# test_circuit1.net
KiCad netlist of a schematic drawn in EAGLE
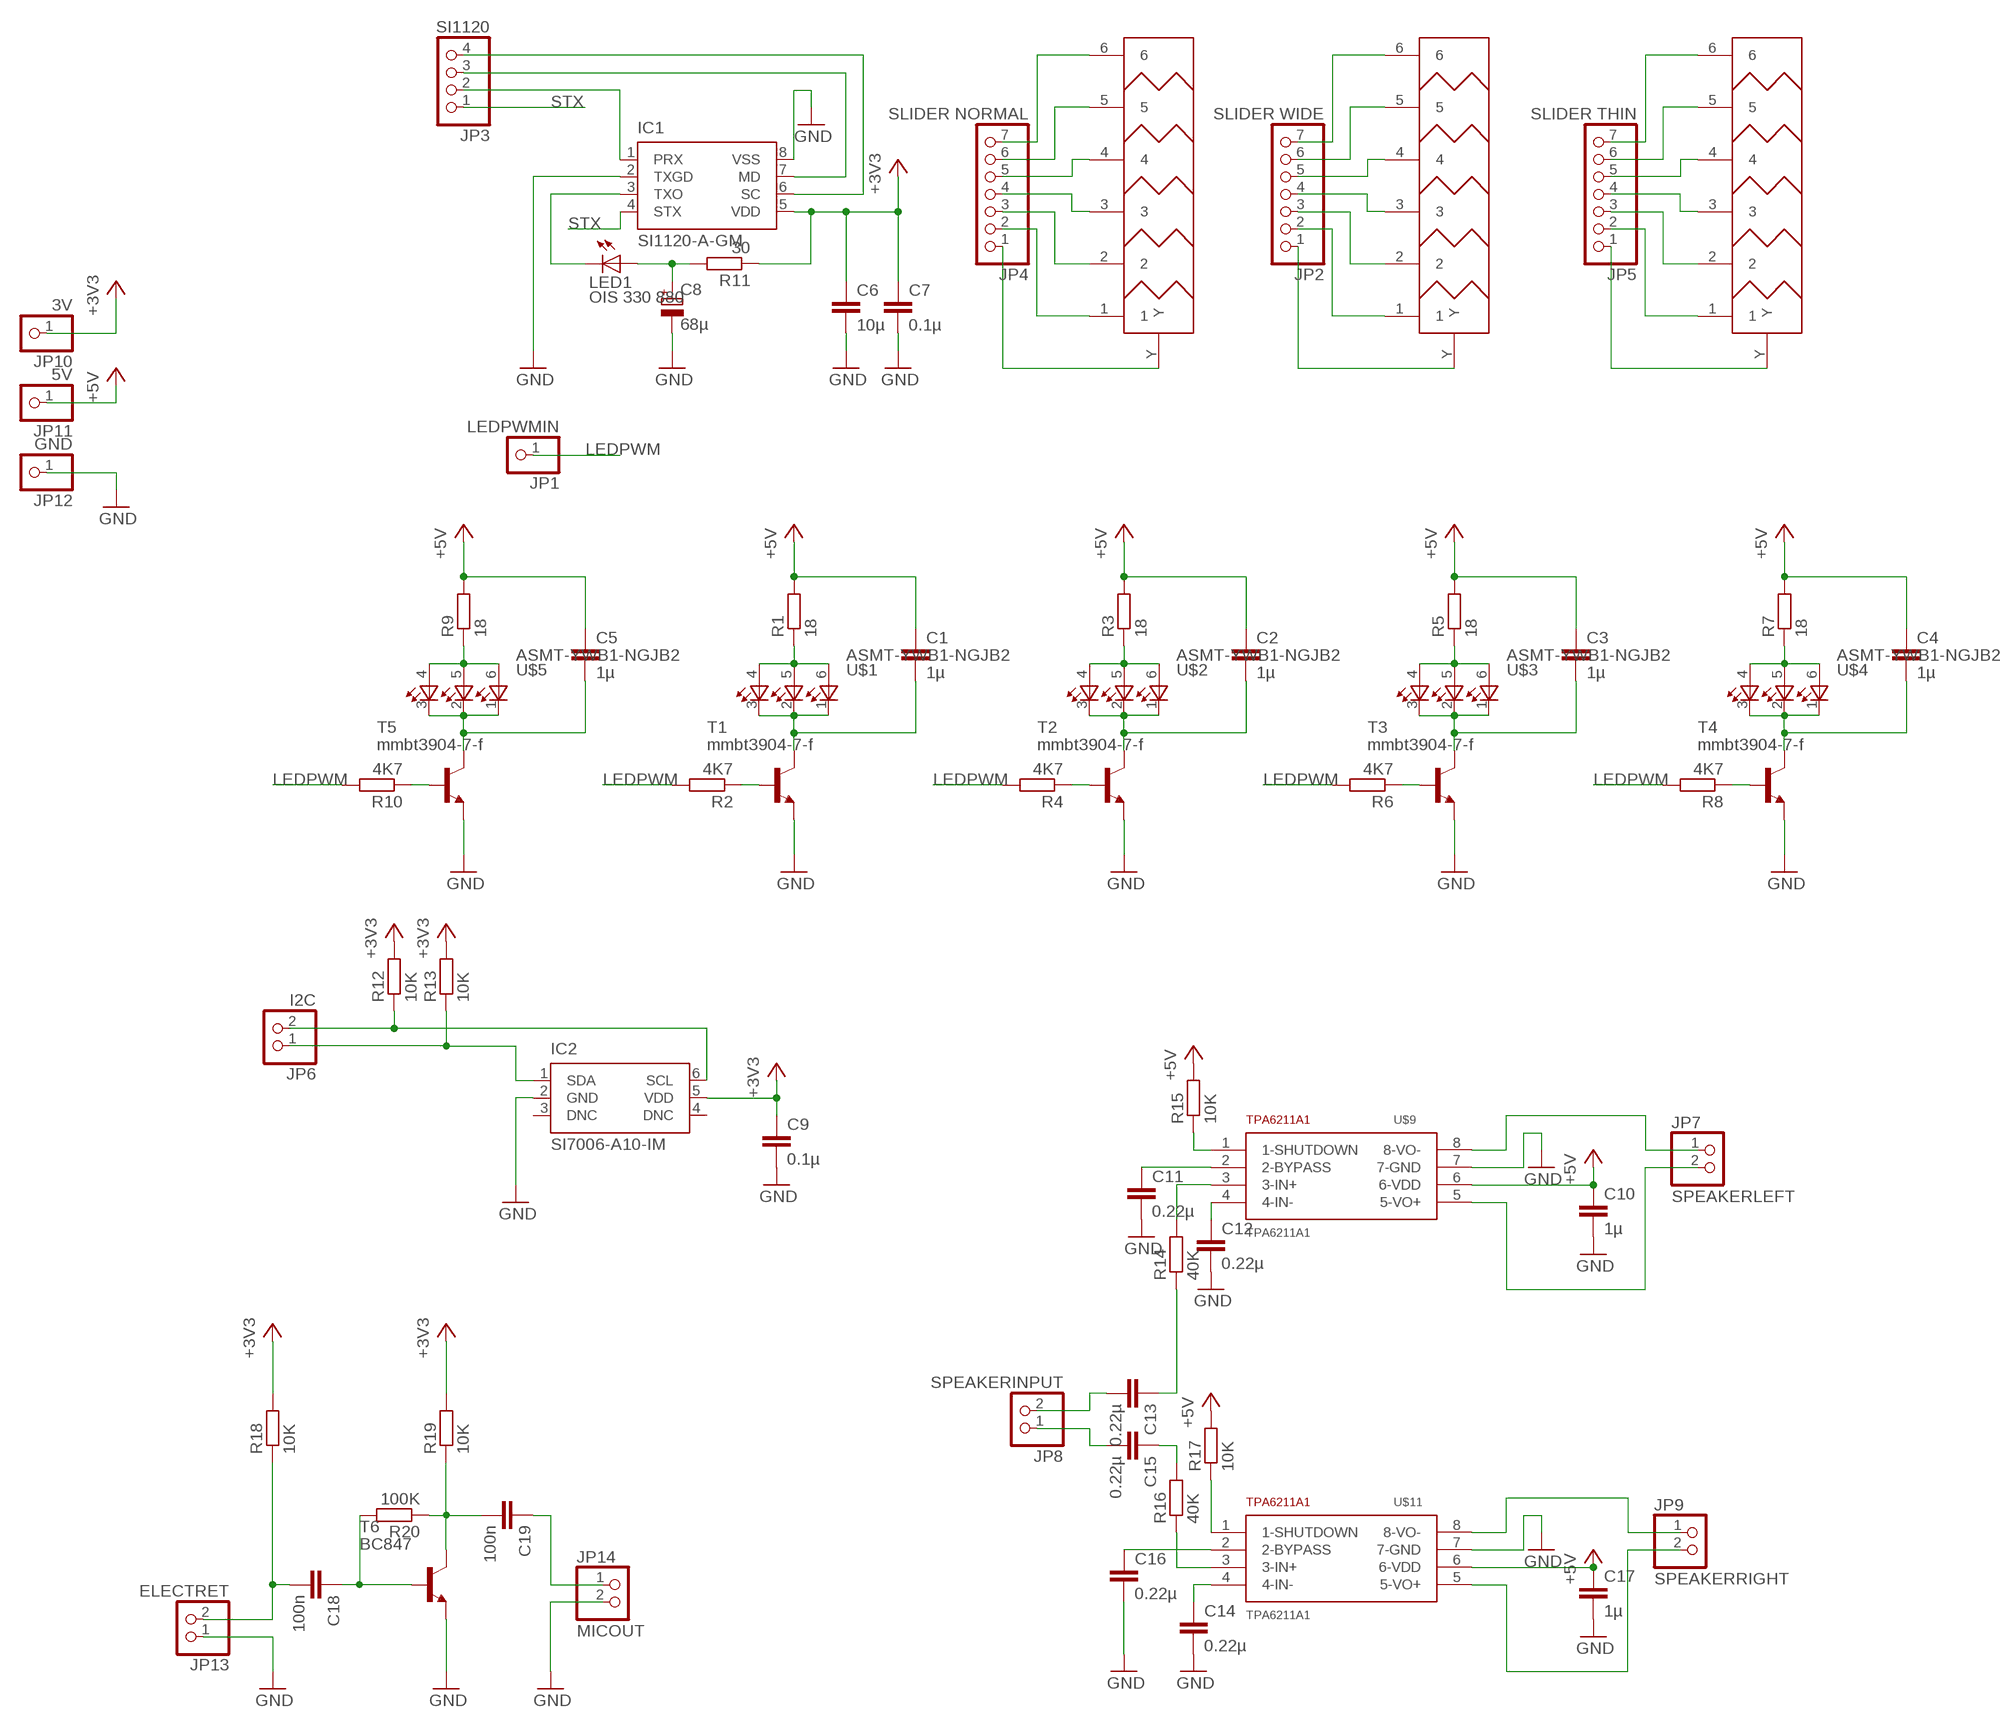
[diagram p0: schematic, sheet 1]

(export (version "E")
  (design (tool "Eeschema 10.0.6"))
  (components
    (comp (ref "C1")
      (value "1µ")
      (footprint "eagle-import:C0805")
      (libsource (lib "eagle-import") (part "C-EUC0805"))
    )
    (comp (ref "C2")
      (value "1µ")
      (footprint "eagle-import:C0805")
      (libsource (lib "eagle-import") (part "C-EUC0805"))
    )
    (comp (ref "C3")
      (value "1µ")
      (footprint "eagle-import:C0805")
      (libsource (lib "eagle-import") (part "C-EUC0805"))
    )
    (comp (ref "C4")
      (value "1µ")
      (footprint "eagle-import:C0805")
      (libsource (lib "eagle-import") (part "C-EUC0805"))
    )
    (comp (ref "C5")
      (value "1µ")
      (footprint "eagle-import:C0805")
      (libsource (lib "eagle-import") (part "C-EUC0805"))
    )
    (comp (ref "C6")
      (value "10µ")
      (footprint "eagle-import:C0805")
      (libsource (lib "eagle-import") (part "C-EUC0805"))
    )
    (comp (ref "C7")
      (value "0.1µ")
      (footprint "eagle-import:C0805")
      (libsource (lib "eagle-import") (part "C-EUC0805"))
    )
    (comp (ref "C8")
      (value "68µ")
      (footprint "eagle-import:E2,5-7")
      (libsource (lib "eagle-import") (part "CPOL-EUE2.5-7"))
    )
    (comp (ref "C9")
      (value "0.1µ")
      (footprint "eagle-import:C0805")
      (libsource (lib "eagle-import") (part "C-EUC0805"))
    )
    (comp (ref "C10")
      (value "1µ")
      (footprint "eagle-import:C0805")
      (libsource (lib "eagle-import") (part "C-EUC0805"))
    )
    (comp (ref "C11")
      (value "0.22µ")
      (footprint "eagle-import:C0805")
      (libsource (lib "eagle-import") (part "C-EUC0805"))
    )
    (comp (ref "C12")
      (value "0.22µ")
      (footprint "eagle-import:C0805")
      (libsource (lib "eagle-import") (part "C-EUC0805"))
    )
    (comp (ref "C13")
      (value "0.22µ")
      (footprint "eagle-import:C0805")
      (libsource (lib "eagle-import") (part "C-EUC0805"))
    )
    (comp (ref "C14")
      (value "0.22µ")
      (footprint "eagle-import:C0805")
      (libsource (lib "eagle-import") (part "C-EUC0805"))
    )
    (comp (ref "C15")
      (value "0.22µ")
      (footprint "eagle-import:C0805")
      (libsource (lib "eagle-import") (part "C-EUC0805"))
    )
    (comp (ref "C16")
      (value "0.22µ")
      (footprint "eagle-import:C0805")
      (libsource (lib "eagle-import") (part "C-EUC0805"))
    )
    (comp (ref "C17")
      (value "1µ")
      (footprint "eagle-import:C0805")
      (libsource (lib "eagle-import") (part "C-EUC0805"))
    )
    (comp (ref "C18")
      (value "100n")
      (footprint "eagle-import:C0805")
      (libsource (lib "eagle-import") (part "C-EUC0805"))
    )
    (comp (ref "C19")
      (value "100n")
      (footprint "eagle-import:C0805")
      (libsource (lib "eagle-import") (part "C-EUC0805"))
    )
    (comp (ref "IC1")
      (value "SI1120-A-GM")
      (footprint "eagle-import:ODFN8-3X3")
      (fields (field (name "MF") "Silicon Labs") (field (name "MPN") "Si1120-A-GM"))
      (libsource (lib "eagle-import") (part "SI1120-A-GM"))
    )
    (comp (ref "IC2")
      (value "SI7006-A10-IM")
      (footprint "eagle-import:DFN6-3X3")
      (fields (field (name "MF") "Silicon Labs") (field (name "MPN") "Si7006-A10-IM"))
      (libsource (lib "eagle-import") (part "SI7006-A10-IM"))
    )
    (comp (ref "JP1")
      (value "LEDPWMIN")
      (footprint "eagle-import:1X01")
      (libsource (lib "eagle-import") (part "PINHD-1X1"))
    )
    (comp (ref "JP2")
      (value "SLIDER WIDE")
      (footprint "eagle-import:1X07")
      (libsource (lib "eagle-import") (part "PINHD-1X7"))
    )
    (comp (ref "JP3")
      (value "SI1120")
      (footprint "eagle-import:1X04")
      (libsource (lib "eagle-import") (part "PINHD-1X4"))
    )
    (comp (ref "JP4")
      (value "SLIDER NORMAL")
      (footprint "eagle-import:1X07")
      (libsource (lib "eagle-import") (part "PINHD-1X7"))
    )
    (comp (ref "JP5")
      (value "SLIDER THIN")
      (footprint "eagle-import:1X07")
      (libsource (lib "eagle-import") (part "PINHD-1X7"))
    )
    (comp (ref "JP6")
      (value "I2C")
      (footprint "eagle-import:1X02")
      (libsource (lib "eagle-import") (part "PINHD-1X2"))
    )
    (comp (ref "JP7")
      (value "SPEAKERLEFT")
      (footprint "eagle-import:1X02")
      (libsource (lib "eagle-import") (part "PINHD-1X2"))
    )
    (comp (ref "JP8")
      (value "SPEAKERINPUT")
      (footprint "eagle-import:1X02")
      (libsource (lib "eagle-import") (part "PINHD-1X2"))
    )
    (comp (ref "JP9")
      (value "SPEAKERRIGHT")
      (footprint "eagle-import:1X02")
      (libsource (lib "eagle-import") (part "PINHD-1X2"))
    )
    (comp (ref "JP10")
      (value "3V")
      (footprint "eagle-import:1X01")
      (libsource (lib "eagle-import") (part "PINHD-1X1"))
    )
    (comp (ref "JP11")
      (value "5V")
      (footprint "eagle-import:1X01")
      (libsource (lib "eagle-import") (part "PINHD-1X1"))
    )
    (comp (ref "JP12")
      (value "GND")
      (footprint "eagle-import:1X01")
      (libsource (lib "eagle-import") (part "PINHD-1X1"))
    )
    (comp (ref "JP13")
      (value "ELECTRET")
      (footprint "eagle-import:1X02")
      (libsource (lib "eagle-import") (part "PINHD-1X2"))
    )
    (comp (ref "JP14")
      (value "MICOUT")
      (footprint "eagle-import:1X02")
      (libsource (lib "eagle-import") (part "PINHD-1X2"))
    )
    (comp (ref "LED1")
      (value "OIS 330 880")
      (footprint "eagle-import:SML1206")
      (libsource (lib "eagle-import") (part "LEDSML1206"))
    )
    (comp (ref "R1")
      (value "18")
      (footprint "eagle-import:R0805")
      (libsource (lib "eagle-import") (part "R-EU_R0805"))
    )
    (comp (ref "R2")
      (value "4K7")
      (footprint "eagle-import:R0805")
      (libsource (lib "eagle-import") (part "R-EU_R0805"))
    )
    (comp (ref "R3")
      (value "18")
      (footprint "eagle-import:R0805")
      (libsource (lib "eagle-import") (part "R-EU_R0805"))
    )
    (comp (ref "R4")
      (value "4K7")
      (footprint "eagle-import:R0805")
      (libsource (lib "eagle-import") (part "R-EU_R0805"))
    )
    (comp (ref "R5")
      (value "18")
      (footprint "eagle-import:R0805")
      (libsource (lib "eagle-import") (part "R-EU_R0805"))
    )
    (comp (ref "R6")
      (value "4K7")
      (footprint "eagle-import:R0805")
      (libsource (lib "eagle-import") (part "R-EU_R0805"))
    )
    (comp (ref "R7")
      (value "18")
      (footprint "eagle-import:R0805")
      (libsource (lib "eagle-import") (part "R-EU_R0805"))
    )
    (comp (ref "R8")
      (value "4K7")
      (footprint "eagle-import:R0805")
      (libsource (lib "eagle-import") (part "R-EU_R0805"))
    )
    (comp (ref "R9")
      (value "18")
      (footprint "eagle-import:R0805")
      (libsource (lib "eagle-import") (part "R-EU_R0805"))
    )
    (comp (ref "R10")
      (value "4K7")
      (footprint "eagle-import:R0805")
      (libsource (lib "eagle-import") (part "R-EU_R0805"))
    )
    (comp (ref "R11")
      (value "30")
      (footprint "eagle-import:R0805")
      (libsource (lib "eagle-import") (part "R-EU_R0805"))
    )
    (comp (ref "R12")
      (value "10K")
      (footprint "eagle-import:R0805")
      (libsource (lib "eagle-import") (part "R-EU_R0805"))
    )
    (comp (ref "R13")
      (value "10K")
      (footprint "eagle-import:R0805")
      (libsource (lib "eagle-import") (part "R-EU_R0805"))
    )
    (comp (ref "R14")
      (value "40K")
      (footprint "eagle-import:R0805")
      (libsource (lib "eagle-import") (part "R-EU_R0805"))
    )
    (comp (ref "R15")
      (value "10K")
      (footprint "eagle-import:R0805")
      (libsource (lib "eagle-import") (part "R-EU_R0805"))
    )
    (comp (ref "R16")
      (value "40K")
      (footprint "eagle-import:R0805")
      (libsource (lib "eagle-import") (part "R-EU_R0805"))
    )
    (comp (ref "R17")
      (value "10K")
      (footprint "eagle-import:R0805")
      (libsource (lib "eagle-import") (part "R-EU_R0805"))
    )
    (comp (ref "R18")
      (value "10K")
      (footprint "eagle-import:R0805")
      (libsource (lib "eagle-import") (part "R-EU_R0805"))
    )
    (comp (ref "R19")
      (value "10K")
      (footprint "eagle-import:R0805")
      (libsource (lib "eagle-import") (part "R-EU_R0805"))
    )
    (comp (ref "R20")
      (value "100K")
      (footprint "eagle-import:R0805")
      (libsource (lib "eagle-import") (part "R-EU_R0805"))
    )
    (comp (ref "T1")
      (value "mmbt3904-7-f")
      (footprint "eagle-import:SOT23-EBC")
      (libsource (lib "eagle-import") (part "-NPN-SOT23-EBC"))
    )
    (comp (ref "T2")
      (value "mmbt3904-7-f")
      (footprint "eagle-import:SOT23-EBC")
      (libsource (lib "eagle-import") (part "-NPN-SOT23-EBC"))
    )
    (comp (ref "T3")
      (value "mmbt3904-7-f")
      (footprint "eagle-import:SOT23-EBC")
      (libsource (lib "eagle-import") (part "-NPN-SOT23-EBC"))
    )
    (comp (ref "T4")
      (value "mmbt3904-7-f")
      (footprint "eagle-import:SOT23-EBC")
      (libsource (lib "eagle-import") (part "-NPN-SOT23-EBC"))
    )
    (comp (ref "T5")
      (value "mmbt3904-7-f")
      (footprint "eagle-import:SOT23-EBC")
      (libsource (lib "eagle-import") (part "-NPN-SOT23-EBC"))
    )
    (comp (ref "T6")
      (value "BC847")
      (footprint "eagle-import:SOT23")
      (libsource (lib "eagle-import") (part "BC847"))
    )
    (comp (ref "U$1")
      (value "ASMT-YWB1-NGJB2")
      (footprint "eagle-import:ASMT-YWB1-NGJB2")
      (libsource (lib "eagle-import") (part "ASMT-YWB1-NGJB2"))
    )
    (comp (ref "U$2")
      (value "ASMT-YWB1-NGJB2")
      (footprint "eagle-import:ASMT-YWB1-NGJB2")
      (libsource (lib "eagle-import") (part "ASMT-YWB1-NGJB2"))
    )
    (comp (ref "U$3")
      (value "ASMT-YWB1-NGJB2")
      (footprint "eagle-import:ASMT-YWB1-NGJB2")
      (libsource (lib "eagle-import") (part "ASMT-YWB1-NGJB2"))
    )
    (comp (ref "U$4")
      (value "ASMT-YWB1-NGJB2")
      (footprint "eagle-import:ASMT-YWB1-NGJB2")
      (libsource (lib "eagle-import") (part "ASMT-YWB1-NGJB2"))
    )
    (comp (ref "U$5")
      (value "ASMT-YWB1-NGJB2")
      (footprint "eagle-import:ASMT-YWB1-NGJB2")
      (libsource (lib "eagle-import") (part "ASMT-YWB1-NGJB2"))
    )
    (comp (ref "U$6")
      (value "SLIDER160MM_RESINT")
      (footprint "eagle-import:SLIDER160MM_RI")
      (libsource (lib "eagle-import") (part "SLIDER160MM_RESINT"))
    )
    (comp (ref "U$7")
      (value "SLIDER16MM_RESINT_WIDEY")
      (footprint "eagle-import:SLIDER160MM_RI_WIDERY")
      (libsource (lib "eagle-import") (part "SLIDER16MM_RESINT_WIDEY"))
    )
    (comp (ref "U$8")
      (value "SLIDER160MM_RESINT_THIN")
      (footprint "eagle-import:SLIDER160MM_RI_THIN")
      (libsource (lib "eagle-import") (part "SLIDER160MM_RESINT_THIN"))
    )
    (comp (ref "U$9")
      (value "TPA6211A1")
      (footprint "eagle-import:MSOP8")
      (libsource (lib "eagle-import") (part "TPA6211A1"))
    )
    (comp (ref "U$11")
      (value "TPA6211A1")
      (footprint "eagle-import:MSOP8")
      (libsource (lib "eagle-import") (part "TPA6211A1"))
    )
  )
  (nets
    (net (code "1") (name "+3V3") (class "Default")
      (node (ref "C6") (pin "1") (pinfunction "1_1") (pintype "passive"))
      (node (ref "C7") (pin "1") (pinfunction "1_1") (pintype "passive"))
      (node (ref "C9") (pin "1") (pinfunction "1_1") (pintype "passive"))
      (node (ref "IC1") (pin "5") (pinfunction "VDD_5") (pintype "power_in"))
      (node (ref "IC2") (pin "5") (pinfunction "VDD_5") (pintype "power_in"))
      (node (ref "JP10") (pin "1") (pinfunction "1_1") (pintype "passive"))
      (node (ref "R11") (pin "1") (pinfunction "1_1") (pintype "passive"))
      (node (ref "R12") (pin "2") (pinfunction "2_2") (pintype "passive"))
      (node (ref "R13") (pin "2") (pinfunction "2_2") (pintype "passive"))
      (node (ref "R18") (pin "2") (pinfunction "2_2") (pintype "passive"))
      (node (ref "R19") (pin "2") (pinfunction "2_2") (pintype "passive"))
    )
    (net (code "2") (name "+5V") (class "Default")
      (node (ref "C1") (pin "1") (pinfunction "1_1") (pintype "passive"))
      (node (ref "C10") (pin "1") (pinfunction "1_1") (pintype "passive"))
      (node (ref "C17") (pin "1") (pinfunction "1_1") (pintype "passive"))
      (node (ref "C2") (pin "1") (pinfunction "1_1") (pintype "passive"))
      (node (ref "C3") (pin "1") (pinfunction "1_1") (pintype "passive"))
      (node (ref "C4") (pin "1") (pinfunction "1_1") (pintype "passive"))
      (node (ref "C5") (pin "1") (pinfunction "1_1") (pintype "passive"))
      (node (ref "JP11") (pin "1") (pinfunction "1_1") (pintype "passive"))
      (node (ref "R1") (pin "2") (pinfunction "2_2") (pintype "passive"))
      (node (ref "R15") (pin "2") (pinfunction "2_2") (pintype "passive"))
      (node (ref "R17") (pin "2") (pinfunction "2_2") (pintype "passive"))
      (node (ref "R3") (pin "2") (pinfunction "2_2") (pintype "passive"))
      (node (ref "R5") (pin "2") (pinfunction "2_2") (pintype "passive"))
      (node (ref "R7") (pin "2") (pinfunction "2_2") (pintype "passive"))
      (node (ref "R9") (pin "2") (pinfunction "2_2") (pintype "passive"))
      (node (ref "U$11") (pin "6") (pinfunction "6-VDD_6") (pintype "bidirectional"))
      (node (ref "U$9") (pin "6") (pinfunction "6-VDD_6") (pintype "bidirectional"))
    )
    (net (code "3") (name "/LEDPWM") (class "Default")
      (node (ref "JP1") (pin "1") (pinfunction "1_1") (pintype "passive"))
      (node (ref "R10") (pin "2") (pinfunction "2_2") (pintype "passive"))
      (node (ref "R2") (pin "2") (pinfunction "2_2") (pintype "passive"))
      (node (ref "R4") (pin "2") (pinfunction "2_2") (pintype "passive"))
      (node (ref "R6") (pin "2") (pinfunction "2_2") (pintype "passive"))
      (node (ref "R8") (pin "2") (pinfunction "2_2") (pintype "passive"))
    )
    (net (code "4") (name "/STX") (class "Default")
      (node (ref "IC1") (pin "4") (pinfunction "STX_4") (pintype "input"))
      (node (ref "JP3") (pin "1") (pinfunction "1_1") (pintype "passive"))
    )
    (net (code "5") (name "GND") (class "Default")
      (node (ref "C10") (pin "2") (pinfunction "2_2") (pintype "passive"))
      (node (ref "C11") (pin "2") (pinfunction "2_2") (pintype "passive"))
      (node (ref "C12") (pin "2") (pinfunction "2_2") (pintype "passive"))
      (node (ref "C14") (pin "2") (pinfunction "2_2") (pintype "passive"))
      (node (ref "C16") (pin "2") (pinfunction "2_2") (pintype "passive"))
      (node (ref "C17") (pin "2") (pinfunction "2_2") (pintype "passive"))
      (node (ref "C6") (pin "2") (pinfunction "2_2") (pintype "passive"))
      (node (ref "C7") (pin "2") (pinfunction "2_2") (pintype "passive"))
      (node (ref "C8") (pin "-") (pinfunction "-_-") (pintype "passive"))
      (node (ref "C9") (pin "2") (pinfunction "2_2") (pintype "passive"))
      (node (ref "IC1") (pin "2") (pinfunction "TXGD_2") (pintype "power_in"))
      (node (ref "IC1") (pin "8") (pinfunction "VSS_8") (pintype "power_in"))
      (node (ref "IC2") (pin "2") (pinfunction "GND_2") (pintype "power_in"))
      (node (ref "JP12") (pin "1") (pinfunction "1_1") (pintype "passive"))
      (node (ref "JP13") (pin "1") (pinfunction "1_1") (pintype "passive"))
      (node (ref "JP14") (pin "2") (pinfunction "2_2") (pintype "passive"))
      (node (ref "T1") (pin "E") (pinfunction "E_E") (pintype "passive"))
      (node (ref "T2") (pin "E") (pinfunction "E_E") (pintype "passive"))
      (node (ref "T3") (pin "E") (pinfunction "E_E") (pintype "passive"))
      (node (ref "T4") (pin "E") (pinfunction "E_E") (pintype "passive"))
      (node (ref "T5") (pin "E") (pinfunction "E_E") (pintype "passive"))
      (node (ref "T6") (pin "2") (pinfunction "E_2") (pintype "passive"))
      (node (ref "U$11") (pin "7") (pinfunction "7-GND_7") (pintype "bidirectional"))
      (node (ref "U$9") (pin "7") (pinfunction "7-GND_7") (pintype "bidirectional"))
    )
    (net (code "6") (name "Net-(C1-Pad2)") (class "Default")
      (node (ref "C1") (pin "2") (pinfunction "2_2") (pintype "passive"))
      (node (ref "T1") (pin "C") (pinfunction "C_C") (pintype "passive"))
      (node (ref "U$1") (pin "1") (pinfunction "1_1") (pintype "passive"))
      (node (ref "U$1") (pin "2") (pinfunction "2_2") (pintype "passive"))
      (node (ref "U$1") (pin "3") (pinfunction "3_3") (pintype "passive"))
    )
    (net (code "7") (name "Net-(C2-Pad2)") (class "Default")
      (node (ref "C2") (pin "2") (pinfunction "2_2") (pintype "passive"))
      (node (ref "T2") (pin "C") (pinfunction "C_C") (pintype "passive"))
      (node (ref "U$2") (pin "1") (pinfunction "1_1") (pintype "passive"))
      (node (ref "U$2") (pin "2") (pinfunction "2_2") (pintype "passive"))
      (node (ref "U$2") (pin "3") (pinfunction "3_3") (pintype "passive"))
    )
    (net (code "8") (name "Net-(C3-Pad2)") (class "Default")
      (node (ref "C3") (pin "2") (pinfunction "2_2") (pintype "passive"))
      (node (ref "T3") (pin "C") (pinfunction "C_C") (pintype "passive"))
      (node (ref "U$3") (pin "1") (pinfunction "1_1") (pintype "passive"))
      (node (ref "U$3") (pin "2") (pinfunction "2_2") (pintype "passive"))
      (node (ref "U$3") (pin "3") (pinfunction "3_3") (pintype "passive"))
    )
    (net (code "9") (name "Net-(C4-Pad2)") (class "Default")
      (node (ref "C4") (pin "2") (pinfunction "2_2") (pintype "passive"))
      (node (ref "T4") (pin "C") (pinfunction "C_C") (pintype "passive"))
      (node (ref "U$4") (pin "1") (pinfunction "1_1") (pintype "passive"))
      (node (ref "U$4") (pin "2") (pinfunction "2_2") (pintype "passive"))
      (node (ref "U$4") (pin "3") (pinfunction "3_3") (pintype "passive"))
    )
    (net (code "10") (name "Net-(C5-Pad2)") (class "Default")
      (node (ref "C5") (pin "2") (pinfunction "2_2") (pintype "passive"))
      (node (ref "T5") (pin "C") (pinfunction "C_C") (pintype "passive"))
      (node (ref "U$5") (pin "1") (pinfunction "1_1") (pintype "passive"))
      (node (ref "U$5") (pin "2") (pinfunction "2_2") (pintype "passive"))
      (node (ref "U$5") (pin "3") (pinfunction "3_3") (pintype "passive"))
    )
    (net (code "11") (name "Net-(C8-Pad+)") (class "Default")
      (node (ref "C8") (pin "+") (pinfunction "+_+") (pintype "passive"))
      (node (ref "LED1") (pin "A") (pinfunction "A_A") (pintype "passive"))
      (node (ref "R11") (pin "2") (pinfunction "2_2") (pintype "passive"))
    )
    (net (code "12") (name "Net-(C13-Pad1)") (class "Default")
      (node (ref "C13") (pin "1") (pinfunction "1_1") (pintype "passive"))
      (node (ref "R14") (pin "1") (pinfunction "1_1") (pintype "passive"))
    )
    (net (code "13") (name "Net-(C13-Pad2)") (class "Default")
      (node (ref "C13") (pin "2") (pinfunction "2_2") (pintype "passive"))
      (node (ref "JP8") (pin "2") (pinfunction "2_2") (pintype "passive"))
    )
    (net (code "14") (name "Net-(C15-Pad1)") (class "Default")
      (node (ref "C15") (pin "1") (pinfunction "1_1") (pintype "passive"))
      (node (ref "R16") (pin "2") (pinfunction "2_2") (pintype "passive"))
    )
    (net (code "15") (name "Net-(C15-Pad2)") (class "Default")
      (node (ref "C15") (pin "2") (pinfunction "2_2") (pintype "passive"))
      (node (ref "JP8") (pin "1") (pinfunction "1_1") (pintype "passive"))
    )
    (net (code "16") (name "Net-(C18-Pad2)") (class "Default")
      (node (ref "C18") (pin "2") (pinfunction "2_2") (pintype "passive"))
      (node (ref "JP13") (pin "2") (pinfunction "2_2") (pintype "passive"))
      (node (ref "R18") (pin "1") (pinfunction "1_1") (pintype "passive"))
    )
    (net (code "17") (name "Net-(C19-Pad1)") (class "Default")
      (node (ref "C19") (pin "1") (pinfunction "1_1") (pintype "passive"))
      (node (ref "JP14") (pin "1") (pinfunction "1_1") (pintype "passive"))
    )
    (net (code "18") (name "Net-(IC1-MD)") (class "Default")
      (node (ref "IC1") (pin "7") (pinfunction "MD_7") (pintype "input"))
      (node (ref "JP3") (pin "3") (pinfunction "3_3") (pintype "passive"))
    )
    (net (code "19") (name "Net-(IC1-PRX)") (class "Default")
      (node (ref "IC1") (pin "1") (pinfunction "PRX_1") (pintype "output"))
      (node (ref "JP3") (pin "2") (pinfunction "2_2") (pintype "passive"))
    )
    (net (code "20") (name "Net-(IC1-SC)") (class "Default")
      (node (ref "IC1") (pin "6") (pinfunction "SC_6") (pintype "input"))
      (node (ref "JP3") (pin "4") (pinfunction "4_4") (pintype "passive"))
    )
    (net (code "21") (name "Net-(IC1-TXO)") (class "Default")
      (node (ref "IC1") (pin "3") (pinfunction "TXO_3") (pintype "output"))
      (node (ref "LED1") (pin "C") (pinfunction "C_C") (pintype "passive"))
    )
    (net (code "22") (name "Net-(IC2-SCL)") (class "Default")
      (node (ref "IC2") (pin "6") (pinfunction "SCL_6") (pintype "input"))
      (node (ref "JP6") (pin "2") (pinfunction "2_2") (pintype "passive"))
      (node (ref "R12") (pin "1") (pinfunction "1_1") (pintype "passive"))
    )
    (net (code "23") (name "Net-(IC2-SDA)") (class "Default")
      (node (ref "IC2") (pin "1") (pinfunction "SDA_1") (pintype "bidirectional"))
      (node (ref "JP6") (pin "1") (pinfunction "1_1") (pintype "passive"))
      (node (ref "R13") (pin "1") (pinfunction "1_1") (pintype "passive"))
    )
    (net (code "24") (name "Net-(JP2-Pad1)") (class "Default")
      (node (ref "JP2") (pin "1") (pinfunction "1_1") (pintype "passive"))
      (node (ref "U$7") (pin "Y") (pinfunction "Y_Y") (pintype "bidirectional"))
    )
    (net (code "25") (name "Net-(JP2-Pad2)") (class "Default")
      (node (ref "JP2") (pin "2") (pinfunction "2_2") (pintype "passive"))
      (node (ref "U$7") (pin "1") (pinfunction "1_1") (pintype "bidirectional"))
    )
    (net (code "26") (name "Net-(JP2-Pad3)") (class "Default")
      (node (ref "JP2") (pin "3") (pinfunction "3_3") (pintype "passive"))
      (node (ref "U$7") (pin "2") (pinfunction "2_2") (pintype "bidirectional"))
    )
    (net (code "27") (name "Net-(JP2-Pad4)") (class "Default")
      (node (ref "JP2") (pin "4") (pinfunction "4_4") (pintype "passive"))
      (node (ref "U$7") (pin "3") (pinfunction "3_3") (pintype "bidirectional"))
    )
    (net (code "28") (name "Net-(JP2-Pad5)") (class "Default")
      (node (ref "JP2") (pin "5") (pinfunction "5_5") (pintype "passive"))
      (node (ref "U$7") (pin "4") (pinfunction "4_4") (pintype "bidirectional"))
    )
    (net (code "29") (name "Net-(JP2-Pad6)") (class "Default")
      (node (ref "JP2") (pin "6") (pinfunction "6_6") (pintype "passive"))
      (node (ref "U$7") (pin "5") (pinfunction "5_5") (pintype "bidirectional"))
    )
    (net (code "30") (name "Net-(JP2-Pad7)") (class "Default")
      (node (ref "JP2") (pin "7") (pinfunction "7_7") (pintype "passive"))
      (node (ref "U$7") (pin "6") (pinfunction "6_6") (pintype "bidirectional"))
    )
    (net (code "31") (name "Net-(JP4-Pad1)") (class "Default")
      (node (ref "JP4") (pin "1") (pinfunction "1_1") (pintype "passive"))
      (node (ref "U$6") (pin "Y") (pinfunction "Y_Y") (pintype "bidirectional"))
    )
    (net (code "32") (name "Net-(JP4-Pad2)") (class "Default")
      (node (ref "JP4") (pin "2") (pinfunction "2_2") (pintype "passive"))
      (node (ref "U$6") (pin "1") (pinfunction "1_1") (pintype "bidirectional"))
    )
    (net (code "33") (name "Net-(JP4-Pad3)") (class "Default")
      (node (ref "JP4") (pin "3") (pinfunction "3_3") (pintype "passive"))
      (node (ref "U$6") (pin "2") (pinfunction "2_2") (pintype "bidirectional"))
    )
    (net (code "34") (name "Net-(JP4-Pad4)") (class "Default")
      (node (ref "JP4") (pin "4") (pinfunction "4_4") (pintype "passive"))
      (node (ref "U$6") (pin "3") (pinfunction "3_3") (pintype "bidirectional"))
    )
    (net (code "35") (name "Net-(JP4-Pad5)") (class "Default")
      (node (ref "JP4") (pin "5") (pinfunction "5_5") (pintype "passive"))
      (node (ref "U$6") (pin "4") (pinfunction "4_4") (pintype "bidirectional"))
    )
    (net (code "36") (name "Net-(JP4-Pad6)") (class "Default")
      (node (ref "JP4") (pin "6") (pinfunction "6_6") (pintype "passive"))
      (node (ref "U$6") (pin "5") (pinfunction "5_5") (pintype "bidirectional"))
    )
    (net (code "37") (name "Net-(JP4-Pad7)") (class "Default")
      (node (ref "JP4") (pin "7") (pinfunction "7_7") (pintype "passive"))
      (node (ref "U$6") (pin "6") (pinfunction "6_6") (pintype "bidirectional"))
    )
    (net (code "38") (name "Net-(JP5-Pad1)") (class "Default")
      (node (ref "JP5") (pin "1") (pinfunction "1_1") (pintype "passive"))
      (node (ref "U$8") (pin "Y") (pinfunction "Y_Y") (pintype "bidirectional"))
    )
    (net (code "39") (name "Net-(JP5-Pad2)") (class "Default")
      (node (ref "JP5") (pin "2") (pinfunction "2_2") (pintype "passive"))
      (node (ref "U$8") (pin "1") (pinfunction "1_1") (pintype "bidirectional"))
    )
    (net (code "40") (name "Net-(JP5-Pad3)") (class "Default")
      (node (ref "JP5") (pin "3") (pinfunction "3_3") (pintype "passive"))
      (node (ref "U$8") (pin "2") (pinfunction "2_2") (pintype "bidirectional"))
    )
    (net (code "41") (name "Net-(JP5-Pad4)") (class "Default")
      (node (ref "JP5") (pin "4") (pinfunction "4_4") (pintype "passive"))
      (node (ref "U$8") (pin "3") (pinfunction "3_3") (pintype "bidirectional"))
    )
    (net (code "42") (name "Net-(JP5-Pad5)") (class "Default")
      (node (ref "JP5") (pin "5") (pinfunction "5_5") (pintype "passive"))
      (node (ref "U$8") (pin "4") (pinfunction "4_4") (pintype "bidirectional"))
    )
    (net (code "43") (name "Net-(JP5-Pad6)") (class "Default")
      (node (ref "JP5") (pin "6") (pinfunction "6_6") (pintype "passive"))
      (node (ref "U$8") (pin "5") (pinfunction "5_5") (pintype "bidirectional"))
    )
    (net (code "44") (name "Net-(JP5-Pad7)") (class "Default")
      (node (ref "JP5") (pin "7") (pinfunction "7_7") (pintype "passive"))
      (node (ref "U$8") (pin "6") (pinfunction "6_6") (pintype "bidirectional"))
    )
    (net (code "45") (name "Net-(R1-Pad1)") (class "Default")
      (node (ref "R1") (pin "1") (pinfunction "1_1") (pintype "passive"))
      (node (ref "U$1") (pin "4") (pinfunction "4_4") (pintype "passive"))
      (node (ref "U$1") (pin "5") (pinfunction "5_5") (pintype "passive"))
      (node (ref "U$1") (pin "6") (pinfunction "6_6") (pintype "passive"))
    )
    (net (code "46") (name "Net-(R2-Pad1)") (class "Default")
      (node (ref "R2") (pin "1") (pinfunction "1_1") (pintype "passive"))
      (node (ref "T1") (pin "B") (pinfunction "B_B") (pintype "passive"))
    )
    (net (code "47") (name "Net-(R3-Pad1)") (class "Default")
      (node (ref "R3") (pin "1") (pinfunction "1_1") (pintype "passive"))
      (node (ref "U$2") (pin "4") (pinfunction "4_4") (pintype "passive"))
      (node (ref "U$2") (pin "5") (pinfunction "5_5") (pintype "passive"))
      (node (ref "U$2") (pin "6") (pinfunction "6_6") (pintype "passive"))
    )
    (net (code "48") (name "Net-(R4-Pad1)") (class "Default")
      (node (ref "R4") (pin "1") (pinfunction "1_1") (pintype "passive"))
      (node (ref "T2") (pin "B") (pinfunction "B_B") (pintype "passive"))
    )
    (net (code "49") (name "Net-(R5-Pad1)") (class "Default")
      (node (ref "R5") (pin "1") (pinfunction "1_1") (pintype "passive"))
      (node (ref "U$3") (pin "4") (pinfunction "4_4") (pintype "passive"))
      (node (ref "U$3") (pin "5") (pinfunction "5_5") (pintype "passive"))
      (node (ref "U$3") (pin "6") (pinfunction "6_6") (pintype "passive"))
    )
    (net (code "50") (name "Net-(R6-Pad1)") (class "Default")
      (node (ref "R6") (pin "1") (pinfunction "1_1") (pintype "passive"))
      (node (ref "T3") (pin "B") (pinfunction "B_B") (pintype "passive"))
    )
    (net (code "51") (name "Net-(R7-Pad1)") (class "Default")
      (node (ref "R7") (pin "1") (pinfunction "1_1") (pintype "passive"))
      (node (ref "U$4") (pin "4") (pinfunction "4_4") (pintype "passive"))
      (node (ref "U$4") (pin "5") (pinfunction "5_5") (pintype "passive"))
      (node (ref "U$4") (pin "6") (pinfunction "6_6") (pintype "passive"))
    )
    (net (code "52") (name "Net-(R8-Pad1)") (class "Default")
      (node (ref "R8") (pin "1") (pinfunction "1_1") (pintype "passive"))
      (node (ref "T4") (pin "B") (pinfunction "B_B") (pintype "passive"))
    )
    (net (code "53") (name "Net-(R9-Pad1)") (class "Default")
      (node (ref "R9") (pin "1") (pinfunction "1_1") (pintype "passive"))
      (node (ref "U$5") (pin "4") (pinfunction "4_4") (pintype "passive"))
      (node (ref "U$5") (pin "5") (pinfunction "5_5") (pintype "passive"))
      (node (ref "U$5") (pin "6") (pinfunction "6_6") (pintype "passive"))
    )
    (net (code "54") (name "Net-(R10-Pad1)") (class "Default")
      (node (ref "R10") (pin "1") (pinfunction "1_1") (pintype "passive"))
      (node (ref "T5") (pin "B") (pinfunction "B_B") (pintype "passive"))
    )
    (net (code "55") (name "Net-(T6-B)") (class "Default")
      (node (ref "C18") (pin "1") (pinfunction "1_1") (pintype "passive"))
      (node (ref "R20") (pin "2") (pinfunction "2_2") (pintype "passive"))
      (node (ref "T6") (pin "1") (pinfunction "B_1") (pintype "passive"))
    )
    (net (code "56") (name "Net-(T6-C)") (class "Default")
      (node (ref "C19") (pin "2") (pinfunction "2_2") (pintype "passive"))
      (node (ref "R19") (pin "1") (pinfunction "1_1") (pintype "passive"))
      (node (ref "R20") (pin "1") (pinfunction "1_1") (pintype "passive"))
      (node (ref "T6") (pin "3") (pinfunction "C_3") (pintype "passive"))
    )
    (net (code "57") (name "Net-(U$9-1-SHUTDOWN)") (class "Default")
      (node (ref "R15") (pin "1") (pinfunction "1_1") (pintype "passive"))
      (node (ref "U$9") (pin "1") (pinfunction "1-SHUTDOWN_1") (pintype "bidirectional"))
    )
    (net (code "58") (name "Net-(U$9-2-BYPASS)") (class "Default")
      (node (ref "C11") (pin "1") (pinfunction "1_1") (pintype "passive"))
      (node (ref "U$9") (pin "2") (pinfunction "2-BYPASS_2") (pintype "bidirectional"))
    )
    (net (code "59") (name "Net-(U$9-3-IN+)") (class "Default")
      (node (ref "R14") (pin "2") (pinfunction "2_2") (pintype "passive"))
      (node (ref "U$9") (pin "3") (pinfunction "3-IN+_3") (pintype "bidirectional"))
    )
    (net (code "60") (name "Net-(U$9-4-IN-)") (class "Default")
      (node (ref "C12") (pin "1") (pinfunction "1_1") (pintype "passive"))
      (node (ref "U$9") (pin "4") (pinfunction "4-IN-_4") (pintype "bidirectional"))
    )
    (net (code "61") (name "Net-(U$9-5-VO+)") (class "Default")
      (node (ref "JP7") (pin "2") (pinfunction "2_2") (pintype "passive"))
      (node (ref "U$9") (pin "5") (pinfunction "5-VO+_5") (pintype "bidirectional"))
    )
    (net (code "62") (name "Net-(U$9-8-VO-)") (class "Default")
      (node (ref "JP7") (pin "1") (pinfunction "1_1") (pintype "passive"))
      (node (ref "U$9") (pin "8") (pinfunction "8-VO-_8") (pintype "bidirectional"))
    )
    (net (code "63") (name "Net-(U$11-1-SHUTDOWN)") (class "Default")
      (node (ref "R17") (pin "1") (pinfunction "1_1") (pintype "passive"))
      (node (ref "U$11") (pin "1") (pinfunction "1-SHUTDOWN_1") (pintype "bidirectional"))
    )
    (net (code "64") (name "Net-(U$11-2-BYPASS)") (class "Default")
      (node (ref "C16") (pin "1") (pinfunction "1_1") (pintype "passive"))
      (node (ref "U$11") (pin "2") (pinfunction "2-BYPASS_2") (pintype "bidirectional"))
    )
    (net (code "65") (name "Net-(U$11-3-IN+)") (class "Default")
      (node (ref "R16") (pin "1") (pinfunction "1_1") (pintype "passive"))
      (node (ref "U$11") (pin "3") (pinfunction "3-IN+_3") (pintype "bidirectional"))
    )
    (net (code "66") (name "Net-(U$11-4-IN-)") (class "Default")
      (node (ref "C14") (pin "1") (pinfunction "1_1") (pintype "passive"))
      (node (ref "U$11") (pin "4") (pinfunction "4-IN-_4") (pintype "bidirectional"))
    )
    (net (code "67") (name "Net-(U$11-5-VO+)") (class "Default")
      (node (ref "JP9") (pin "2") (pinfunction "2_2") (pintype "passive"))
      (node (ref "U$11") (pin "5") (pinfunction "5-VO+_5") (pintype "bidirectional"))
    )
    (net (code "68") (name "Net-(U$11-8-VO-)") (class "Default")
      (node (ref "JP9") (pin "1") (pinfunction "1_1") (pintype "passive"))
      (node (ref "U$11") (pin "8") (pinfunction "8-VO-_8") (pintype "bidirectional"))
    )
    (net (code "69") (name "unconnected-(IC2-DNC-Pad3)") (class "Default")
      (node (ref "IC2") (pin "3") (pinfunction "DNC_3") (pintype "no_connect"))
    )
    (net (code "70") (name "unconnected-(IC2-DNC-Pad4)") (class "Default")
      (node (ref "IC2") (pin "4") (pinfunction "DNC_4") (pintype "no_connect"))
    )
  )
)
